# Cum_LED_v2.net
KiCad netlist of a schematic drawn in Altium Designer
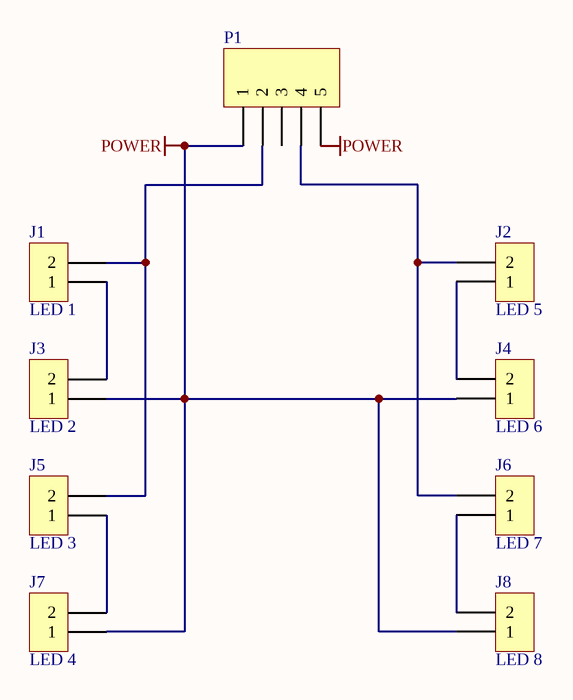
[diagram p0: Cum LED v2.SchDoc]

(export (version "E")
  (design (tool "Eeschema 10.0.6"))
  (components
    (comp (ref "J1")
      (value "LED 1")
      (footprint "LED OSRAM CIRCUIT")
      (fields (field (name "Comment") "Jump đực loại cong, 2.54mmLED 1"))
      (libsource (lib "") (part "CON2_1"))
    )
    (comp (ref "J2")
      (value "LED 5")
      (footprint "LED OSRAM CIRCUIT")
      (fields (field (name "Comment") "Jump đực loại cong, 2.54mmLED 5"))
      (libsource (lib "DnsSchLib") (part "CON2"))
    )
    (comp (ref "J3")
      (value "LED 2")
      (footprint "LED OSRAM CIRCUIT")
      (fields (field (name "Comment") "Jump đực loại cong, 2.54mmLED 2"))
      (libsource (lib "") (part "CON2_1"))
    )
    (comp (ref "J4")
      (value "LED 6")
      (footprint "LED OSRAM CIRCUIT")
      (fields (field (name "Comment") "Jump đực loại cong, 2.54mmLED 6"))
      (libsource (lib "DnsSchLib") (part "CON2"))
    )
    (comp (ref "J5")
      (value "LED 3")
      (footprint "LED OSRAM CIRCUIT")
      (fields (field (name "Comment") "Jump đực loại cong, 2.54mmLED 3"))
      (libsource (lib "") (part "CON2_1"))
    )
    (comp (ref "J6")
      (value "LED 7")
      (footprint "LED OSRAM CIRCUIT")
      (fields (field (name "Comment") "Jump đực loại cong, 2.54mmLED 7"))
      (libsource (lib "DnsSchLib") (part "CON2"))
    )
    (comp (ref "J7")
      (value "LED 4")
      (footprint "LED OSRAM CIRCUIT")
      (fields (field (name "Comment") "Jump đực loại cong, 2.54mmLED 4"))
      (libsource (lib "") (part "CON2_1"))
    )
    (comp (ref "J8")
      (value "LED 8")
      (footprint "LED OSRAM CIRCUIT")
      (fields (field (name "Comment") "Jump đực loại cong, 2.54mmLED 8"))
      (libsource (lib "DnsSchLib") (part "CON2"))
    )
    (comp (ref "P1")
      (value "Jump đực loại thẳng, 2.54mm 5P")
      (footprint "HDR1X5")
      (description "Header, 5-Pin")
      (fields (field (name "PUBLISHER") "Altium Limited"))
      (libsource (lib "Miscellaneous Connectors") (part "Header 5"))
    )
  )
  (nets
    (net (code "1") (name "Net-(J1-Pad1)") (class "Default")
      (node (ref "J1") (pin "1") (pinfunction "1_1") (pintype "passive"))
      (node (ref "J3") (pin "2") (pinfunction "2_2") (pintype "passive"))
    )
    (net (code "2") (name "Net-(J1-Pad2)") (class "Default")
      (node (ref "J1") (pin "2") (pinfunction "2_2") (pintype "passive"))
      (node (ref "J5") (pin "2") (pinfunction "2_2") (pintype "passive"))
      (node (ref "P1") (pin "2") (pinfunction "2_2") (pintype "passive"))
    )
    (net (code "3") (name "Net-(J2-Pad1)") (class "Default")
      (node (ref "J2") (pin "1") (pinfunction "1_1") (pintype "passive"))
      (node (ref "J4") (pin "2") (pinfunction "2_2") (pintype "passive"))
    )
    (net (code "4") (name "Net-(J2-Pad2)") (class "Default")
      (node (ref "J2") (pin "2") (pinfunction "2_2") (pintype "passive"))
      (node (ref "J6") (pin "2") (pinfunction "2_2") (pintype "passive"))
      (node (ref "P1") (pin "4") (pinfunction "4_4") (pintype "passive"))
    )
    (net (code "5") (name "Net-(J5-Pad1)") (class "Default")
      (node (ref "J5") (pin "1") (pinfunction "1_1") (pintype "passive"))
      (node (ref "J7") (pin "2") (pinfunction "2_2") (pintype "passive"))
    )
    (net (code "6") (name "Net-(J6-Pad1)") (class "Default")
      (node (ref "J6") (pin "1") (pinfunction "1_1") (pintype "passive"))
      (node (ref "J8") (pin "2") (pinfunction "2_2") (pintype "passive"))
    )
    (net (code "7") (name "POWER") (class "Default")
      (node (ref "J3") (pin "1") (pinfunction "1_1") (pintype "passive"))
      (node (ref "J4") (pin "1") (pinfunction "1_1") (pintype "passive"))
      (node (ref "J7") (pin "1") (pinfunction "1_1") (pintype "passive"))
      (node (ref "J8") (pin "1") (pinfunction "1_1") (pintype "passive"))
      (node (ref "P1") (pin "1") (pinfunction "1_1") (pintype "passive"))
      (node (ref "P1") (pin "5") (pinfunction "5_5") (pintype "passive"))
    )
    (net (code "8") (name "unconnected-(P1-Pad3)") (class "Default")
      (node (ref "P1") (pin "3") (pinfunction "3_3") (pintype "passive"))
    )
  )
)
